# MCU.net
KiCad netlist of a schematic drawn in Altium Designer
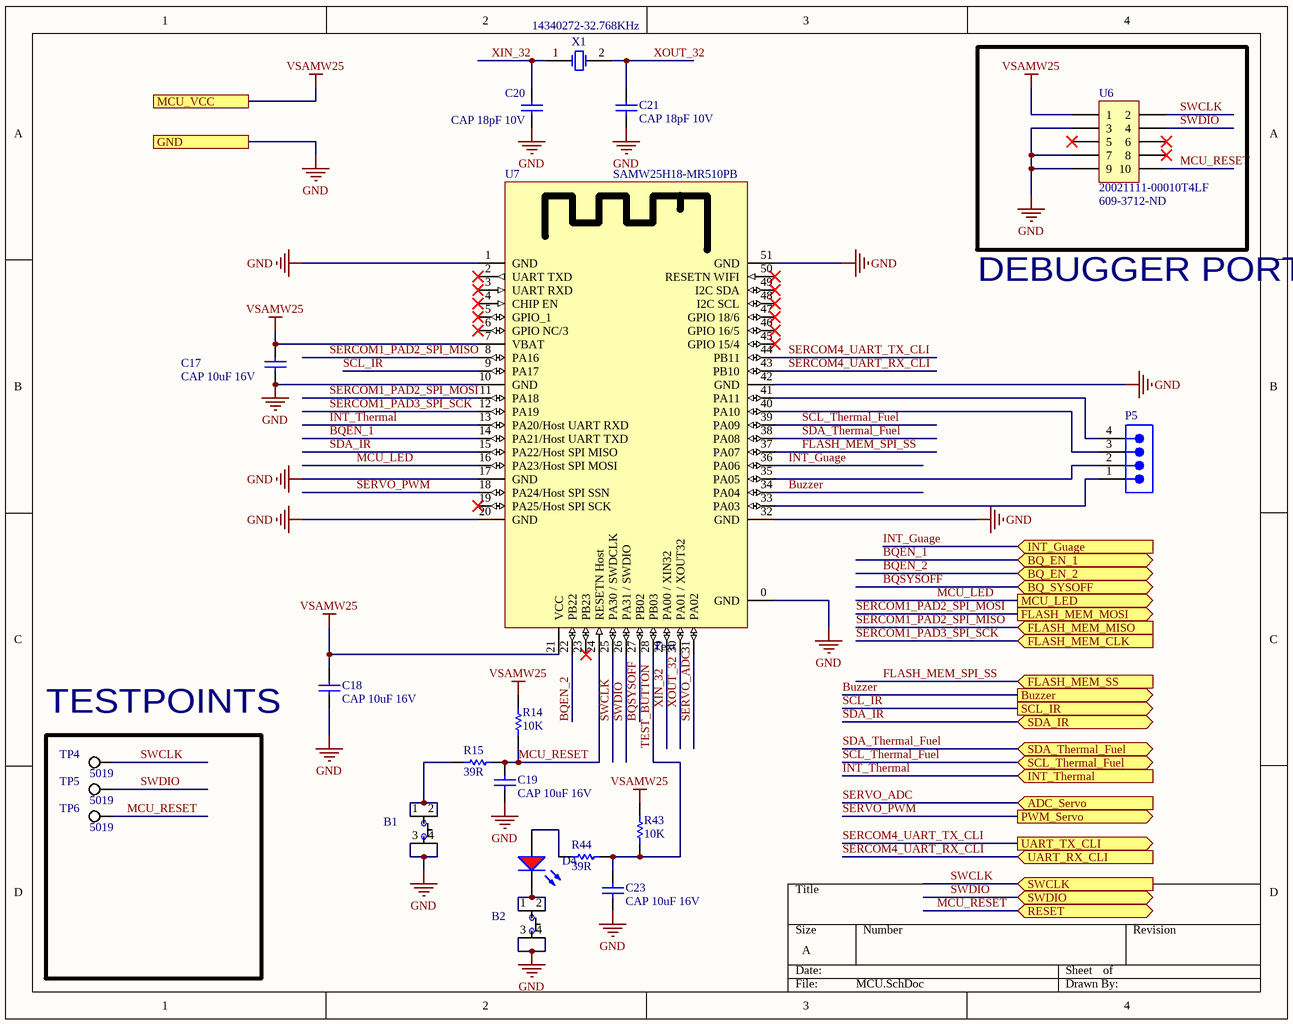
[diagram p0: MCU.SchDoc]

(export (version "E")
  (design (tool "Eeschema 10.0.6"))
  (components
    (comp (ref "B1")
      (value "PTS810 SJK 250 SMTR LFS")
      (footprint "PTS810 SJK 250 SMTR LFS")
      (description "SWITCH TACTILE SPST-NO 0.05A 16V Tactile Switch SPST-NO Top Actuated Surface Mount")
      (fields
        (field (name "MANUFACTURER") "ITT /  C&K Components")
        (field (name "MANUFACTURER PART NUMBER") "PTS810SJK250SMTRLFS")
      )
      (libsource (lib "Schematics") (part "PTS810 SJK 250 SMTR LFS"))
    )
    (comp (ref "B2")
      (value "PTS810 SJK 250 SMTR LFS")
      (footprint "PTS810 SJK 250 SMTR LFS")
      (description "SWITCH TACTILE SPST-NO 0.05A 16V Tactile Switch SPST-NO Top Actuated Surface Mount")
      (fields
        (field (name "MANUFACTURER") "ITT /  C&K Components")
        (field (name "MANUFACTURER PART NUMBER") "PTS810SJK250SMTRLFS")
      )
      (libsource (lib "Schematics") (part "PTS810 SJK 250 SMTR LFS"))
    )
    (comp (ref "C17")
      (value "CAP 10uF 16V")
      (footprint "CAPC0805(2012)145_L")
      (description "CAP 10uF 16V ±10% 0805 (2012 Metric) Thickness 1.45mm SMD")
      (fields (field (name "TOLERANCE") "Â±10%"))
      (libsource (lib "Altium Content Vault") (part "CAP"))
    )
    (comp (ref "C18")
      (value "CAP 10uF 16V")
      (footprint "CAPC0805(2012)145_L")
      (description "CAP 10uF 16V ±10% 0805 (2012 Metric) Thickness 1.45mm SMD")
      (fields (field (name "TOLERANCE") "Â±10%"))
      (libsource (lib "Altium Content Vault") (part "CAP"))
    )
    (comp (ref "C19")
      (value "CAP 10uF 16V")
      (footprint "CAPC0805(2012)145_L")
      (description "CAP 10uF 16V ±10% 0805 (2012 Metric) Thickness 1.45mm SMD")
      (fields (field (name "TOLERANCE") "Â±10%"))
      (libsource (lib "Altium Content Vault") (part "CAP"))
    )
    (comp (ref "C20")
      (value "CAP 18pF 10V")
      (footprint "CAPC0805(2012)75_L")
      (description "CAP 18pF 10V ±1% 0805 (2012 Metric) Thickness 0.75mm SMD")
      (fields (field (name "TOLERANCE") "Â±1%"))
      (libsource (lib "Altium Content Vault") (part "CAP"))
    )
    (comp (ref "C21")
      (value "CAP 18pF 10V")
      (footprint "CAPC0805(2012)75_L")
      (description "CAP 18pF 10V ±1% 0805 (2012 Metric) Thickness 0.75mm SMD")
      (fields (field (name "TOLERANCE") "Â±1%"))
      (libsource (lib "Altium Content Vault") (part "CAP"))
    )
    (comp (ref "C23")
      (value "CAP 10uF 16V")
      (footprint "CAPC0805(2012)145_L")
      (description "CAP 10uF 16V ±10% 0805 (2012 Metric) Thickness 1.45mm SMD")
      (fields (field (name "TOLERANCE") "Â±10%"))
      (libsource (lib "Altium Content Vault") (part "CAP"))
    )
    (comp (ref "D4")
      (value "~")
      (footprint "LTST-C170CKT_V")
      (description "LED RED CLEAR 0805 SMD")
      (fields (field (name "MANUFACTURER") "Lite-On") (field (name "PARTNUMBER") "LTST-C170CKT"))
      (libsource (lib "Altium Content Vault") (part "LED_RED_AC"))
    )
    (comp (ref "P5")
      (value "~")
      (footprint "SMTC-MTSW-104-07-X-S-170")
      (fields (field (name "MANUFACTURER") "Samtec") (field (name "PARTNUMBER") "MTSW-104-07-L-S-170"))
      (libsource (lib "Altium Content Vault") (part "SMTC-MTSW-104-07-X-S-170"))
    )
    (comp (ref "R14")
      (value "10K")
      (footprint "RESC0402(1005)_M")
      (description "10K 0.063W 5% 0402 (1005 Metric)  SMD")
      (fields (field (name "TOLERANCE") "5 %") (field (name "POWER") "0.063 W"))
      (libsource (lib "Altium Content Vault") (part "CMP-1011-00098-1"))
    )
    (comp (ref "R15")
      (value "39R")
      (footprint "RESC0805(2012)_N")
      (description "39R 0.125W 5% 0805 (2012 Metric)  SMD")
      (fields (field (name "POWER") "0.125 W") (field (name "TOLERANCE") "5 %"))
      (libsource (lib "Altium Content Vault") (part "RES"))
    )
    (comp (ref "R43")
      (value "10K")
      (footprint "RESC0402(1005)_M")
      (description "10K 0.063W 5% 0402 (1005 Metric)  SMD")
      (fields (field (name "TOLERANCE") "5 %") (field (name "POWER") "0.063 W"))
      (libsource (lib "Altium Content Vault") (part "CMP-1011-00098-1"))
    )
    (comp (ref "R44")
      (value "39R")
      (footprint "RESC0805(2012)_N")
      (description "39R 0.125W 5% 0805 (2012 Metric)  SMD")
      (fields (field (name "POWER") "0.125 W") (field (name "TOLERANCE") "5 %"))
      (libsource (lib "Altium Content Vault") (part "RES"))
    )
    (comp (ref "TP4")
      (value "5019")
      (footprint "KSTN-5019_V")
      (description "Test Point, 1 Position SMD, RoHS, Tape and Reel")
      (libsource (lib "Altium Content Vault") (part "TESTPOINT_WHITE"))
    )
    (comp (ref "TP5")
      (value "5019")
      (footprint "KSTN-5019_V")
      (description "Test Point, 1 Position SMD, RoHS, Tape and Reel")
      (libsource (lib "Altium Content Vault") (part "TESTPOINT_WHITE"))
    )
    (comp (ref "TP6")
      (value "5019")
      (footprint "KSTN-5019_V")
      (description "Test Point, 1 Position SMD, RoHS, Tape and Reel")
      (libsource (lib "Altium Content Vault") (part "TESTPOINT_WHITE"))
    )
    (comp (ref "U6")
      (value "20021111-00010T4LF")
      (footprint "20021111-00010T4LF")
      (description "CONN HEADER 10POS UNSHD VERT T/H")
      (fields
        (field (name "MANUFACTURER") "Amphenol / FCI")
        (field (name "SUPPLIER PART NUMBER 1") "609-3712-ND")
      )
      (libsource (lib "Schematics") (part "20021111-00010T4LF"))
    )
    (comp (ref "U7")
      (value "SAMW25H18-MR510PB")
      (footprint "SAMW25H18-MR510PB")
      (description "RF TXRX MODULE WIFI TRACE ANT")
      (fields
        (field (name "MANUFACTURER") "Atmel")
        (field (name "MANUFACTURER PART NUMBER") "ATSAMW25H18-MR510PB")
      )
      (libsource (lib "Schematics") (part "SAMW25H18-MR510PB"))
    )
    (comp (ref "X1")
      (value "14340272-32.768KHz")
      (footprint "ITTI-14340272-32.768KHz-2_V")
      (description "Crystal, 32.768 KHz, -40 to 85 degC, 3.2 x 1.5 x 0.9 mm SMD")
      (fields (field (name "MANUFACTURER") "ITTI"))
      (libsource (lib "Altium Content Vault") (part "ITTI-14340272-2"))
    )
  )
  (nets
    (net (code "2") (name "/BQEN_1") (class "Default")
      (node (ref "U7") (pin "14") (pinfunction "PA21/Host_UART_TXD_14") (pintype "bidirectional"))
    )
    (net (code "3") (name "/BQEN_2") (class "Default")
      (node (ref "U7") (pin "22") (pinfunction "PB22_22") (pintype "bidirectional"))
    )
    (net (code "4") (name "/BQSYSOFF") (class "Default")
      (node (ref "U7") (pin "27") (pinfunction "PB02_27") (pintype "bidirectional"))
    )
    (net (code "5") (name "/Buzzer") (class "Default")
      (node (ref "U7") (pin "34") (pinfunction "PA04_34") (pintype "bidirectional"))
    )
    (net (code "6") (name "/FLASH_MEM_SPI_SS") (class "Default")
      (node (ref "U7") (pin "37") (pinfunction "PA07_37") (pintype "bidirectional"))
    )
    (net (code "7") (name "/INT_Guage") (class "Default")
      (node (ref "U7") (pin "36") (pinfunction "PA06_36") (pintype "bidirectional"))
    )
    (net (code "8") (name "/INT_Thermal") (class "Default")
      (node (ref "U7") (pin "13") (pinfunction "PA20/Host_UART_RXD_13") (pintype "bidirectional"))
    )
    (net (code "9") (name "/MCU_LED") (class "Default")
      (node (ref "U7") (pin "16") (pinfunction "PA23/Host_SPI_MOSI_16") (pintype "bidirectional"))
    )
    (net (code "10") (name "/MCU_RESET") (class "Default")
      (node (ref "C19") (pin "2") (pinfunction "2_2") (pintype "passive"))
      (node (ref "R14") (pin "2") (pinfunction "2_2") (pintype "passive"))
      (node (ref "R15") (pin "1") (pinfunction "1_1") (pintype "passive"))
      (node (ref "TP6") (pin "1") (pinfunction "1_1") (pintype "passive"))
      (node (ref "U6") (pin "10") (pinfunction "10_10") (pintype "passive"))
      (node (ref "U7") (pin "24") (pinfunction "RESETN_Host_24") (pintype "input"))
    )
    (net (code "11") (name "/SCL_IR") (class "Default")
      (node (ref "U7") (pin "9") (pinfunction "PA17_9") (pintype "bidirectional"))
    )
    (net (code "12") (name "/SCL_Thermal_Fuel") (class "Default")
      (node (ref "U7") (pin "39") (pinfunction "PA09_39") (pintype "bidirectional"))
    )
    (net (code "13") (name "/SDA_IR") (class "Default")
      (node (ref "U7") (pin "15") (pinfunction "PA22/Host_SPI_MISO_15") (pintype "bidirectional"))
    )
    (net (code "14") (name "/SDA_Thermal_Fuel") (class "Default")
      (node (ref "U7") (pin "38") (pinfunction "PA08_38") (pintype "bidirectional"))
    )
    (net (code "15") (name "/SERCOM1_PAD2_SPI_MISO") (class "Default")
      (node (ref "U7") (pin "8") (pinfunction "PA16_8") (pintype "bidirectional"))
    )
    (net (code "16") (name "/SERCOM1_PAD2_SPI_MOSI") (class "Default")
      (node (ref "U7") (pin "11") (pinfunction "PA18_11") (pintype "bidirectional"))
    )
    (net (code "17") (name "/SERCOM1_PAD3_SPI_SCK") (class "Default")
      (node (ref "U7") (pin "12") (pinfunction "PA19_12") (pintype "bidirectional"))
    )
    (net (code "18") (name "/SERCOM4_UART_RX_CLI") (class "Default")
      (node (ref "U7") (pin "43") (pinfunction "PB10_43") (pintype "bidirectional"))
    )
    (net (code "19") (name "/SERCOM4_UART_TX_CLI") (class "Default")
      (node (ref "U7") (pin "44") (pinfunction "PB11_44") (pintype "bidirectional"))
    )
    (net (code "20") (name "/SERVO_ADC") (class "Default")
      (node (ref "U7") (pin "31") (pinfunction "PA02_31") (pintype "bidirectional"))
    )
    (net (code "21") (name "/SERVO_PWM") (class "Default")
      (node (ref "U7") (pin "18") (pinfunction "PA24/Host_SPI_SSN_18") (pintype "bidirectional"))
    )
    (net (code "22") (name "/SWCLK") (class "Default")
      (node (ref "TP4") (pin "1") (pinfunction "1_1") (pintype "passive"))
      (node (ref "U6") (pin "2") (pinfunction "2_2") (pintype "passive"))
      (node (ref "U7") (pin "25") (pinfunction "PA30_/_SWDCLK_25") (pintype "bidirectional"))
    )
    (net (code "23") (name "/SWDIO") (class "Default")
      (node (ref "TP5") (pin "1") (pinfunction "1_1") (pintype "passive"))
      (node (ref "U6") (pin "4") (pinfunction "4_4") (pintype "passive"))
      (node (ref "U7") (pin "26") (pinfunction "PA31_/_SWDIO_26") (pintype "bidirectional"))
    )
    (net (code "24") (name "/TEST_BUTTON") (class "Default")
      (node (ref "C23") (pin "2") (pinfunction "2_2") (pintype "passive"))
      (node (ref "R43") (pin "2") (pinfunction "2_2") (pintype "passive"))
      (node (ref "R44") (pin "1") (pinfunction "1_1") (pintype "passive"))
      (node (ref "U7") (pin "28") (pinfunction "PB03_28") (pintype "bidirectional"))
    )
    (net (code "25") (name "/XIN_32") (class "Default")
      (node (ref "C20") (pin "1") (pinfunction "1_1") (pintype "passive"))
      (node (ref "U7") (pin "29") (pinfunction "PA00_/_XIN32_29") (pintype "bidirectional"))
      (node (ref "X1") (pin "1") (pinfunction "X1_1") (pintype "passive"))
    )
    (net (code "26") (name "/XOUT_32") (class "Default")
      (node (ref "C21") (pin "1") (pinfunction "1_1") (pintype "passive"))
      (node (ref "U7") (pin "30") (pinfunction "PA01_/_XOUT32_30") (pintype "bidirectional"))
      (node (ref "X1") (pin "2") (pinfunction "X2_2") (pintype "passive"))
    )
    (net (code "27") (name "GND") (class "Default")
      (node (ref "B1") (pin "3") (pinfunction "3_3") (pintype "power_in"))
      (node (ref "B1") (pin "4") (pinfunction "4_4") (pintype "power_in"))
      (node (ref "B2") (pin "3") (pinfunction "3_3") (pintype "power_in"))
      (node (ref "B2") (pin "4") (pinfunction "4_4") (pintype "power_in"))
      (node (ref "C17") (pin "1") (pinfunction "1_1") (pintype "passive"))
      (node (ref "C18") (pin "1") (pinfunction "1_1") (pintype "passive"))
      (node (ref "C19") (pin "1") (pinfunction "1_1") (pintype "passive"))
      (node (ref "C20") (pin "2") (pinfunction "2_2") (pintype "passive"))
      (node (ref "C21") (pin "2") (pinfunction "2_2") (pintype "passive"))
      (node (ref "C23") (pin "1") (pinfunction "1_1") (pintype "passive"))
      (node (ref "U6") (pin "3") (pinfunction "3_3") (pintype "passive"))
      (node (ref "U6") (pin "7") (pinfunction "7_7") (pintype "passive"))
      (node (ref "U6") (pin "9") (pinfunction "9_9") (pintype "passive"))
      (node (ref "U7") (pin "0") (pinfunction "GND_0") (pintype "power_in"))
      (node (ref "U7") (pin "1") (pinfunction "GND_1") (pintype "power_in"))
      (node (ref "U7") (pin "10") (pinfunction "GND_10") (pintype "power_in"))
      (node (ref "U7") (pin "17") (pinfunction "GND_17") (pintype "power_in"))
      (node (ref "U7") (pin "20") (pinfunction "GND_20") (pintype "power_in"))
      (node (ref "U7") (pin "32") (pinfunction "GND_32") (pintype "power_in"))
      (node (ref "U7") (pin "42") (pinfunction "GND_42") (pintype "power_in"))
      (node (ref "U7") (pin "51") (pinfunction "GND_51") (pintype "power_in"))
    )
    (net (code "28") (name "Net-(B1-Pad1)") (class "Default")
      (node (ref "B1") (pin "1") (pinfunction "1_1") (pintype "power_in"))
      (node (ref "B1") (pin "2") (pinfunction "2_2") (pintype "power_in"))
      (node (ref "R15") (pin "2") (pinfunction "2_2") (pintype "passive"))
    )
    (net (code "29") (name "Net-(B2-Pad1)") (class "Default")
      (node (ref "B2") (pin "1") (pinfunction "1_1") (pintype "power_in"))
      (node (ref "B2") (pin "2") (pinfunction "2_2") (pintype "power_in"))
      (node (ref "D4") (pin "C") (pinfunction "C_C") (pintype "passive"))
    )
    (net (code "30") (name "Net-(D4-PadA)") (class "Default")
      (node (ref "D4") (pin "A") (pinfunction "A_A") (pintype "passive"))
      (node (ref "R44") (pin "2") (pinfunction "2_2") (pintype "passive"))
    )
    (net (code "31") (name "Net-(U7-PA03)") (class "Default")
      (node (ref "P5") (pin "1") (pinfunction "1_1") (pintype "passive"))
      (node (ref "U7") (pin "33") (pinfunction "PA03_33") (pintype "bidirectional"))
    )
    (net (code "32") (name "Net-(U7-PA05)") (class "Default")
      (node (ref "P5") (pin "2") (pinfunction "2_2") (pintype "passive"))
      (node (ref "U7") (pin "35") (pinfunction "PA05_35") (pintype "bidirectional"))
    )
    (net (code "33") (name "Net-(U7-PA10)") (class "Default")
      (node (ref "P5") (pin "3") (pinfunction "3_3") (pintype "passive"))
      (node (ref "U7") (pin "40") (pinfunction "PA10_40") (pintype "bidirectional"))
    )
    (net (code "34") (name "Net-(U7-PA11)") (class "Default")
      (node (ref "P5") (pin "4") (pinfunction "4_4") (pintype "passive"))
      (node (ref "U7") (pin "41") (pinfunction "PA11_41") (pintype "bidirectional"))
    )
    (net (code "35") (name "VSAMW25") (class "Default")
      (node (ref "C17") (pin "2") (pinfunction "2_2") (pintype "passive"))
      (node (ref "C18") (pin "2") (pinfunction "2_2") (pintype "passive"))
      (node (ref "R14") (pin "1") (pinfunction "1_1") (pintype "passive"))
      (node (ref "R43") (pin "1") (pinfunction "1_1") (pintype "passive"))
      (node (ref "U6") (pin "1") (pinfunction "1_1") (pintype "passive"))
      (node (ref "U7") (pin "21") (pinfunction "VCC_21") (pintype "power_in"))
      (node (ref "U7") (pin "7") (pinfunction "VBAT_7") (pintype "power_in"))
    )
    (net (code "36") (name "unconnected-(U6-Pad5)") (class "Default")
      (node (ref "U6") (pin "5") (pinfunction "5_5") (pintype "passive+no_connect"))
    )
    (net (code "37") (name "unconnected-(U6-Pad6)") (class "Default")
      (node (ref "U6") (pin "6") (pinfunction "6_6") (pintype "passive+no_connect"))
    )
    (net (code "38") (name "unconnected-(U6-Pad8)") (class "Default")
      (node (ref "U6") (pin "8") (pinfunction "8_8") (pintype "passive+no_connect"))
    )
    (net (code "39") (name "unconnected-(U7-CHIP_EN-Pad4)") (class "Default")
      (node (ref "U7") (pin "4") (pinfunction "CHIP_EN_4") (pintype "input+no_connect"))
    )
    (net (code "40") (name "unconnected-(U7-GPIO_1-Pad5)") (class "Default")
      (node (ref "U7") (pin "5") (pinfunction "GPIO_1_5") (pintype "bidirectional+no_connect"))
    )
    (net (code "41") (name "unconnected-(U7-GPIO_15{slash}4-Pad45)") (class "Default")
      (node (ref "U7") (pin "45") (pinfunction "GPIO_15/4_45") (pintype "bidirectional+no_connect"))
    )
    (net (code "42") (name "unconnected-(U7-GPIO_16{slash}5-Pad46)") (class "Default")
      (node (ref "U7") (pin "46") (pinfunction "GPIO_16/5_46") (pintype "bidirectional+no_connect"))
    )
    (net (code "43") (name "unconnected-(U7-GPIO_18{slash}6-Pad47)") (class "Default")
      (node (ref "U7") (pin "47") (pinfunction "GPIO_18/6_47") (pintype "bidirectional+no_connect"))
    )
    (net (code "44") (name "unconnected-(U7-GPIO_NC{slash}3-Pad6)") (class "Default")
      (node (ref "U7") (pin "6") (pinfunction "GPIO_NC/3_6") (pintype "bidirectional+no_connect"))
    )
    (net (code "45") (name "unconnected-(U7-I2C_SCL-Pad48)") (class "Default")
      (node (ref "U7") (pin "48") (pinfunction "I2C_SCL_48") (pintype "bidirectional+no_connect"))
    )
    (net (code "46") (name "unconnected-(U7-I2C_SDA-Pad49)") (class "Default")
      (node (ref "U7") (pin "49") (pinfunction "I2C_SDA_49") (pintype "bidirectional+no_connect"))
    )
    (net (code "47") (name "unconnected-(U7-PA25{slash}Host_SPI_SCK-Pad19)") (class "Default")
      (node (ref "U7") (pin "19") (pinfunction "PA25/Host_SPI_SCK_19") (pintype "bidirectional+no_connect"))
    )
    (net (code "48") (name "unconnected-(U7-PB23-Pad23)") (class "Default")
      (node (ref "U7") (pin "23") (pinfunction "PB23_23") (pintype "bidirectional+no_connect"))
    )
    (net (code "49") (name "unconnected-(U7-RESETN_WIFI-Pad50)") (class "Default")
      (node (ref "U7") (pin "50") (pinfunction "RESETN_WIFI_50") (pintype "input+no_connect"))
    )
    (net (code "50") (name "unconnected-(U7-UART_RXD-Pad3)") (class "Default")
      (node (ref "U7") (pin "3") (pinfunction "UART_RXD_3") (pintype "input+no_connect"))
    )
    (net (code "51") (name "unconnected-(U7-UART_TXD-Pad2)") (class "Default")
      (node (ref "U7") (pin "2") (pinfunction "UART_TXD_2") (pintype "output+no_connect"))
    )
  )
)
